# Kilobot_Controller_CPU.net
KiCad netlist of a schematic drawn in Altium Designer
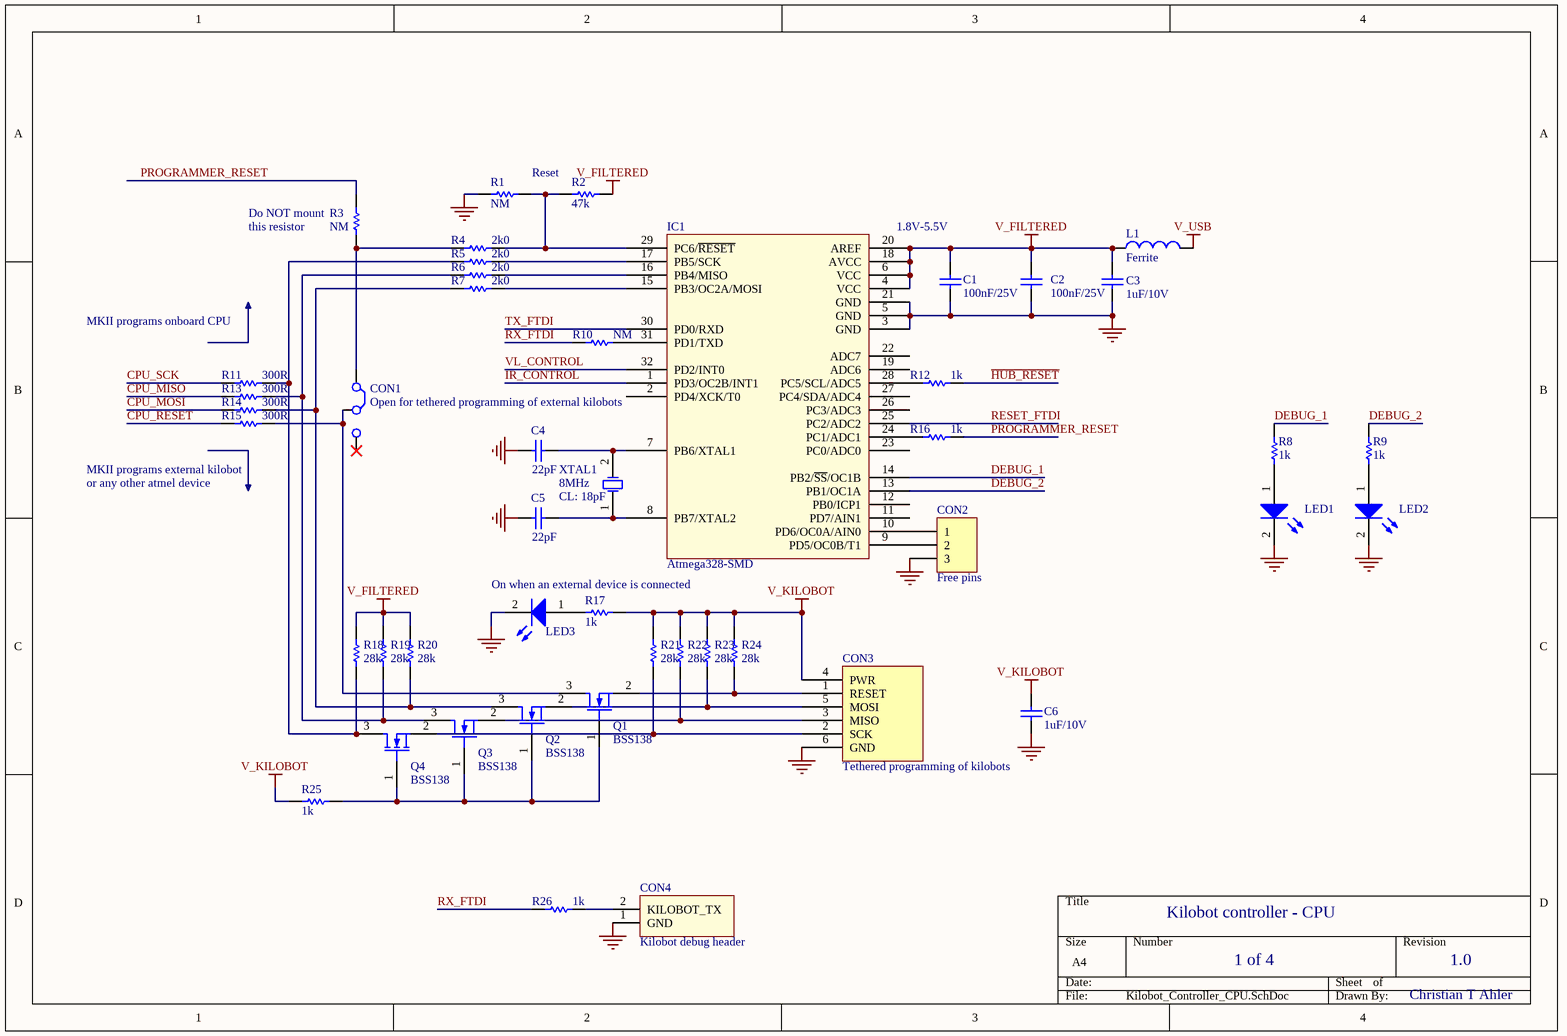
[diagram p0: Kilobot_Controller_CPU.SchDoc]

(export (version "E")
  (design (tool "Eeschema 10.0.6"))
  (components
    (comp (ref "C1")
      (value "100nF/25V")
      (footprint "RESC1608L")
      (description "Ceramic Chip Capacitor - Standard")
      (fields (field (name "Comment") "C0603"))
      (libsource (lib "KEMET Chip Capacitor") (part "C0603"))
    )
    (comp (ref "C2")
      (value "100nF/25V")
      (footprint "RESC1608L")
      (description "Ceramic Chip Capacitor - Standard")
      (fields (field (name "Comment") "C0603"))
      (libsource (lib "KEMET Chip Capacitor") (part "C0603"))
    )
    (comp (ref "C3")
      (value "1uF/10V")
      (footprint "RESC1608L")
      (description "Ceramic Chip Capacitor - Standard")
      (fields (field (name "Comment") "C0603"))
      (libsource (lib "KEMET Chip Capacitor") (part "C0603"))
    )
    (comp (ref "C4")
      (value "22pF")
      (footprint "RESC1608L")
      (description "Ceramic Chip Capacitor - Standard")
      (fields (field (name "Comment") "C0603"))
      (libsource (lib "KEMET Chip Capacitor") (part "C0603"))
    )
    (comp (ref "C5")
      (value "22pF")
      (footprint "RESC1608L")
      (description "Ceramic Chip Capacitor - Standard")
      (fields (field (name "Comment") "C0603"))
      (libsource (lib "KEMET Chip Capacitor") (part "C0603"))
    )
    (comp (ref "C6")
      (value "1uF/10V")
      (footprint "RESC1608L")
      (description "Ceramic Chip Capacitor - Standard")
      (fields (field (name "Comment") "C0603"))
      (libsource (lib "KEMET Chip Capacitor") (part "C0603"))
    )
    (comp (ref "CON1")
      (value "~")
      (footprint "Miscellaneous Connectors:HDR1X3")
      (libsource (lib "Kilobot_Controller") (part "Jumper3"))
    )
    (comp (ref "CON2")
      (value "Free pins")
      (footprint "HDR1X3")
      (description "Header, 3-Pin")
      (libsource (lib "Miscellaneous Connectors") (part "Header 3"))
    )
    (comp (ref "CON3")
      (value "Tethered programming of kilobots")
      (footprint "Programming")
      (libsource (lib "Kilobot_Controller") (part "Programming con new symbol"))
    )
    (comp (ref "CON4")
      (value "Kilobot debug header")
      (footprint "HDR1X2")
      (libsource (lib "Kilobot_Controller") (part "Kilobot_Debug_Header"))
    )
    (comp (ref "IC1")
      (value "Atmega328-SMD")
      (footprint "TQFP32")
      (libsource (lib "Programmer") (part "Atmega328-SMD"))
    )
    (comp (ref "L1")
      (value "Ferrite")
      (footprint "RESC2012N")
      (description "Inductor")
      (libsource (lib "Miscellaneous Devices") (part "Inductor"))
    )
    (comp (ref "LED1") (value "LED") (footprint "LED0603") (libsource (lib "KilobotCommercial") (part "LED")))
    (comp (ref "LED2") (value "LED") (footprint "LED0603") (libsource (lib "KilobotCommercial") (part "LED")))
    (comp (ref "LED3") (value "LED") (footprint "LED0603") (libsource (lib "KilobotCommercial") (part "LED")))
    (comp (ref "Q1")
      (value "BSS138")
      (footprint "sot23-3")
      (fields (field (name "Comment") "NMOS23"))
      (libsource (lib "KilobotCommercial") (part "NMOS23"))
    )
    (comp (ref "Q2")
      (value "BSS138")
      (footprint "sot23-3")
      (fields (field (name "Comment") "NMOS23"))
      (libsource (lib "KilobotCommercial") (part "NMOS23"))
    )
    (comp (ref "Q3")
      (value "BSS138")
      (footprint "sot23-3")
      (fields (field (name "Comment") "NMOS23"))
      (libsource (lib "KilobotCommercial") (part "NMOS23"))
    )
    (comp (ref "Q4")
      (value "BSS138")
      (footprint "sot23-3")
      (fields (field (name "Comment") "NMOS23"))
      (libsource (lib "KilobotCommercial") (part "NMOS23"))
    )
    (comp (ref "R1")
      (value "NM")
      (footprint "RESC1608L")
      (description "Resistor")
      (fields (field (name "Comment") "Res1"))
      (libsource (lib "Miscellaneous Devices") (part "Res1"))
    )
    (comp (ref "R2")
      (value "47k")
      (footprint "RESC1608L")
      (description "Resistor")
      (fields (field (name "Comment") "Res1"))
      (libsource (lib "Miscellaneous Devices") (part "Res1"))
    )
    (comp (ref "R3")
      (value "NM")
      (footprint "RESC1608L")
      (description "Resistor")
      (fields (field (name "Comment") "Res1"))
      (libsource (lib "Miscellaneous Devices") (part "Res1"))
    )
    (comp (ref "R4")
      (value "2k0")
      (footprint "RESC1608L")
      (description "Resistor")
      (fields (field (name "Comment") "Res1"))
      (libsource (lib "Miscellaneous Devices") (part "Res1"))
    )
    (comp (ref "R5")
      (value "2k0")
      (footprint "RESC1608L")
      (description "Resistor")
      (fields (field (name "Comment") "Res1"))
      (libsource (lib "Miscellaneous Devices") (part "Res1"))
    )
    (comp (ref "R6")
      (value "2k0")
      (footprint "RESC1608L")
      (description "Resistor")
      (fields (field (name "Comment") "Res1"))
      (libsource (lib "Miscellaneous Devices") (part "Res1"))
    )
    (comp (ref "R7")
      (value "2k0")
      (footprint "RESC1608L")
      (description "Resistor")
      (fields (field (name "Comment") "Res1"))
      (libsource (lib "Miscellaneous Devices") (part "Res1"))
    )
    (comp (ref "R8")
      (value "1k")
      (footprint "RESC1608L")
      (description "Resistor")
      (fields (field (name "Comment") "Res1"))
      (libsource (lib "Miscellaneous Devices") (part "Res1"))
    )
    (comp (ref "R9")
      (value "1k")
      (footprint "RESC1608L")
      (description "Resistor")
      (fields (field (name "Comment") "Res1"))
      (libsource (lib "Miscellaneous Devices") (part "Res1"))
    )
    (comp (ref "R10")
      (value "NM")
      (footprint "RESC1608L")
      (description "Resistor")
      (fields (field (name "Comment") "Res1"))
      (libsource (lib "Miscellaneous Devices") (part "Res1"))
    )
    (comp (ref "R11")
      (value "300R")
      (footprint "RESC1608L")
      (description "Resistor")
      (fields (field (name "Comment") "Res1"))
      (libsource (lib "Miscellaneous Devices") (part "Res1"))
    )
    (comp (ref "R12")
      (value "1k")
      (footprint "RESC1608L")
      (description "Resistor")
      (fields (field (name "Comment") "Res1"))
      (libsource (lib "Miscellaneous Devices") (part "Res1"))
    )
    (comp (ref "R13")
      (value "300R")
      (footprint "RESC1608L")
      (description "Resistor")
      (fields (field (name "Comment") "Res1"))
      (libsource (lib "Miscellaneous Devices") (part "Res1"))
    )
    (comp (ref "R14")
      (value "300R")
      (footprint "RESC1608L")
      (description "Resistor")
      (fields (field (name "Comment") "Res1"))
      (libsource (lib "Miscellaneous Devices") (part "Res1"))
    )
    (comp (ref "R15")
      (value "300R")
      (footprint "RESC1608L")
      (description "Resistor")
      (fields (field (name "Comment") "Res1"))
      (libsource (lib "Miscellaneous Devices") (part "Res1"))
    )
    (comp (ref "R16")
      (value "1k")
      (footprint "RESC1608L")
      (description "Resistor")
      (fields (field (name "Comment") "Res1"))
      (libsource (lib "Miscellaneous Devices") (part "Res1"))
    )
    (comp (ref "R17")
      (value "1k")
      (footprint "RESC1608L")
      (description "Resistor")
      (fields (field (name "Comment") "Res1"))
      (libsource (lib "Miscellaneous Devices") (part "Res1"))
    )
    (comp (ref "R18")
      (value "28k")
      (footprint "RESC1608L")
      (description "Resistor")
      (fields (field (name "Comment") "Res1"))
      (libsource (lib "Miscellaneous Devices") (part "Res1"))
    )
    (comp (ref "R19")
      (value "28k")
      (footprint "RESC1608L")
      (description "Resistor")
      (fields (field (name "Comment") "Res1"))
      (libsource (lib "Miscellaneous Devices") (part "Res1"))
    )
    (comp (ref "R20")
      (value "28k")
      (footprint "RESC1608L")
      (description "Resistor")
      (fields (field (name "Comment") "Res1"))
      (libsource (lib "Miscellaneous Devices") (part "Res1"))
    )
    (comp (ref "R21")
      (value "28k")
      (footprint "RESC1608L")
      (description "Resistor")
      (fields (field (name "Comment") "Res1"))
      (libsource (lib "Miscellaneous Devices") (part "Res1"))
    )
    (comp (ref "R22")
      (value "28k")
      (footprint "RESC1608L")
      (description "Resistor")
      (fields (field (name "Comment") "Res1"))
      (libsource (lib "Miscellaneous Devices") (part "Res1"))
    )
    (comp (ref "R23")
      (value "28k")
      (footprint "RESC1608L")
      (description "Resistor")
      (fields (field (name "Comment") "Res1"))
      (libsource (lib "Miscellaneous Devices") (part "Res1"))
    )
    (comp (ref "R24")
      (value "28k")
      (footprint "RESC1608L")
      (description "Resistor")
      (fields (field (name "Comment") "Res1"))
      (libsource (lib "Miscellaneous Devices") (part "Res1"))
    )
    (comp (ref "R25")
      (value "1k")
      (footprint "RESC1608L")
      (description "Resistor")
      (fields (field (name "Comment") "Res1"))
      (libsource (lib "Miscellaneous Devices") (part "Res1"))
    )
    (comp (ref "R26")
      (value "1k")
      (footprint "RESC1608L")
      (description "Resistor")
      (fields (field (name "Comment") "Res1"))
      (libsource (lib "Miscellaneous Devices") (part "Res1"))
    )
    (comp (ref "XTAL1")
      (value "8MHz")
      (footprint "crystal-hc49")
      (fields (field (name "CL") "18pF") (field (name "Comment") "Crystal"))
      (libsource (lib "Programmer") (part "Crystal"))
    )
  )
  (nets
    (net (code "1") (name "/CPU_MISO") (class "Default")
      (node (ref "R13") (pin "2") (pinfunction "2_2") (pintype "passive"))
    )
    (net (code "2") (name "/CPU_MOSI") (class "Default")
      (node (ref "R14") (pin "2") (pinfunction "2_2") (pintype "passive"))
    )
    (net (code "3") (name "/CPU_RESET") (class "Default")
      (node (ref "R15") (pin "2") (pinfunction "2_2") (pintype "passive"))
    )
    (net (code "4") (name "/CPU_SCK") (class "Default")
      (node (ref "R11") (pin "2") (pinfunction "2_2") (pintype "passive"))
    )
    (net (code "5") (name "/DEBUG_1") (class "Default")
      (node (ref "IC1") (pin "14") (pinfunction "PB2/~{SS}/OC1B_14") (pintype "passive"))
      (node (ref "R8") (pin "2") (pinfunction "2_2") (pintype "passive"))
    )
    (net (code "6") (name "/DEBUG_2") (class "Default")
      (node (ref "IC1") (pin "13") (pinfunction "PB1/OC1A_13") (pintype "passive"))
      (node (ref "R9") (pin "2") (pinfunction "2_2") (pintype "passive"))
    )
    (net (code "7") (name "/IR_CONTROL") (class "Default")
      (node (ref "IC1") (pin "1") (pinfunction "PD3/OC2B/INT1_1") (pintype "passive"))
    )
    (net (code "8") (name "/PROGRAMMER_RESET") (class "Default")
      (node (ref "R16") (pin "2") (pinfunction "2_2") (pintype "passive"))
      (node (ref "R3") (pin "2") (pinfunction "2_2") (pintype "passive"))
    )
    (net (code "9") (name "/RESET_FTDI") (class "Default")
      (node (ref "IC1") (pin "25") (pinfunction "PC2/ADC2_25") (pintype "passive"))
    )
    (net (code "10") (name "/RX_FTDI") (class "Default")
      (node (ref "R10") (pin "2") (pinfunction "2_2") (pintype "passive"))
      (node (ref "R26") (pin "2") (pinfunction "2_2") (pintype "passive"))
    )
    (net (code "11") (name "/TX_FTDI") (class "Default")
      (node (ref "IC1") (pin "30") (pinfunction "PD0/RXD_30") (pintype "passive"))
    )
    (net (code "12") (name "/VL_CONTROL") (class "Default")
      (node (ref "IC1") (pin "32") (pinfunction "PD2/INT0_32") (pintype "passive"))
    )
    (net (code "13") (name "/~{HUB_RESET}") (class "Default")
      (node (ref "R12") (pin "2") (pinfunction "2_2") (pintype "passive"))
    )
    (net (code "14") (name "GND") (class "Default")
      (node (ref "C1") (pin "2") (pinfunction "2_2") (pintype "passive"))
      (node (ref "C2") (pin "2") (pinfunction "2_2") (pintype "passive"))
      (node (ref "C3") (pin "1") (pinfunction "1_1") (pintype "passive"))
      (node (ref "C4") (pin "1") (pinfunction "1_1") (pintype "passive"))
      (node (ref "C5") (pin "1") (pinfunction "1_1") (pintype "passive"))
      (node (ref "C6") (pin "2") (pinfunction "2_2") (pintype "passive"))
      (node (ref "CON2") (pin "3") (pinfunction "3_3") (pintype "passive"))
      (node (ref "CON3") (pin "6") (pinfunction "GND_6") (pintype "passive"))
      (node (ref "CON4") (pin "1") (pinfunction "GND_1") (pintype "passive"))
      (node (ref "IC1") (pin "21") (pinfunction "GND_21") (pintype "passive"))
      (node (ref "IC1") (pin "3") (pinfunction "GND_3") (pintype "passive"))
      (node (ref "IC1") (pin "5") (pinfunction "GND_5") (pintype "passive"))
      (node (ref "LED1") (pin "2") (pinfunction "K_2") (pintype "passive"))
      (node (ref "LED2") (pin "2") (pinfunction "K_2") (pintype "passive"))
      (node (ref "LED3") (pin "2") (pinfunction "K_2") (pintype "passive"))
      (node (ref "R1") (pin "2") (pinfunction "2_2") (pintype "passive"))
    )
    (net (code "15") (name "Net-(CON1-C1)") (class "Default")
      (node (ref "CON1") (pin "1") (pinfunction "C1_1") (pintype "passive"))
      (node (ref "R3") (pin "1") (pinfunction "1_1") (pintype "passive"))
      (node (ref "R4") (pin "2") (pinfunction "2_2") (pintype "passive"))
    )
    (net (code "16") (name "Net-(CON1-C2)") (class "Default")
      (node (ref "CON1") (pin "2") (pinfunction "C2_2") (pintype "passive"))
      (node (ref "Q1") (pin "3") (pinfunction "D_3") (pintype "passive"))
      (node (ref "R15") (pin "1") (pinfunction "1_1") (pintype "passive"))
    )
    (net (code "17") (name "Net-(CON3-MISO)") (class "Default")
      (node (ref "CON3") (pin "3") (pinfunction "MISO_3") (pintype "passive"))
      (node (ref "Q3") (pin "2") (pinfunction "S_2") (pintype "passive"))
      (node (ref "R22") (pin "1") (pinfunction "1_1") (pintype "passive"))
    )
    (net (code "18") (name "Net-(CON3-MOSI)") (class "Default")
      (node (ref "CON3") (pin "5") (pinfunction "MOSI_5") (pintype "passive"))
      (node (ref "Q2") (pin "2") (pinfunction "S_2") (pintype "passive"))
      (node (ref "R23") (pin "1") (pinfunction "1_1") (pintype "passive"))
    )
    (net (code "19") (name "Net-(CON3-RESET)") (class "Default")
      (node (ref "CON3") (pin "1") (pinfunction "RESET_1") (pintype "passive"))
      (node (ref "Q1") (pin "2") (pinfunction "S_2") (pintype "passive"))
      (node (ref "R24") (pin "1") (pinfunction "1_1") (pintype "passive"))
    )
    (net (code "20") (name "Net-(CON3-SCK)") (class "Default")
      (node (ref "CON3") (pin "2") (pinfunction "SCK_2") (pintype "passive"))
      (node (ref "Q4") (pin "2") (pinfunction "S_2") (pintype "passive"))
      (node (ref "R21") (pin "1") (pinfunction "1_1") (pintype "passive"))
    )
    (net (code "21") (name "Net-(CON4-KILOBOT_TX)") (class "Default")
      (node (ref "CON4") (pin "2") (pinfunction "KILOBOT_TX_2") (pintype "passive"))
      (node (ref "R26") (pin "1") (pinfunction "1_1") (pintype "passive"))
    )
    (net (code "22") (name "Net-(IC1-PB3{slash}OC2A{slash}MOSI)") (class "Default")
      (node (ref "IC1") (pin "15") (pinfunction "PB3/OC2A/MOSI_15") (pintype "passive"))
      (node (ref "R7") (pin "1") (pinfunction "1_1") (pintype "passive"))
    )
    (net (code "23") (name "Net-(IC1-PB4{slash}MISO)") (class "Default")
      (node (ref "IC1") (pin "16") (pinfunction "PB4/MISO_16") (pintype "passive"))
      (node (ref "R6") (pin "1") (pinfunction "1_1") (pintype "passive"))
    )
    (net (code "24") (name "Net-(IC1-PB5{slash}SCK)") (class "Default")
      (node (ref "IC1") (pin "17") (pinfunction "PB5/SCK_17") (pintype "passive"))
      (node (ref "R5") (pin "1") (pinfunction "1_1") (pintype "passive"))
    )
    (net (code "25") (name "Net-(IC1-PB6{slash}XTAL1)") (class "Default")
      (node (ref "C4") (pin "2") (pinfunction "2_2") (pintype "passive"))
      (node (ref "IC1") (pin "7") (pinfunction "PB6/XTAL1_7") (pintype "passive"))
      (node (ref "XTAL1") (pin "2") (pinfunction "OSC2_2") (pintype "passive"))
    )
    (net (code "26") (name "Net-(IC1-PB7{slash}XTAL2)") (class "Default")
      (node (ref "C5") (pin "2") (pinfunction "2_2") (pintype "passive"))
      (node (ref "IC1") (pin "8") (pinfunction "PB7/XTAL2_8") (pintype "passive"))
      (node (ref "XTAL1") (pin "1") (pinfunction "OSC1_1") (pintype "passive"))
    )
    (net (code "27") (name "Net-(IC1-PC1{slash}ADC1)") (class "Default")
      (node (ref "IC1") (pin "24") (pinfunction "PC1/ADC1_24") (pintype "passive"))
      (node (ref "R16") (pin "1") (pinfunction "1_1") (pintype "passive"))
    )
    (net (code "28") (name "Net-(IC1-PC5{slash}SCL{slash}ADC5)") (class "Default")
      (node (ref "IC1") (pin "28") (pinfunction "PC5/SCL/ADC5_28") (pintype "passive"))
      (node (ref "R12") (pin "1") (pinfunction "1_1") (pintype "passive"))
    )
    (net (code "29") (name "Net-(IC1-PC6{slash}~{RESET})") (class "Default")
      (node (ref "IC1") (pin "29") (pinfunction "PC6/~{RESET}_29") (pintype "passive"))
      (node (ref "R1") (pin "1") (pinfunction "1_1") (pintype "passive"))
      (node (ref "R2") (pin "2") (pinfunction "2_2") (pintype "passive"))
      (node (ref "R4") (pin "1") (pinfunction "1_1") (pintype "passive"))
    )
    (net (code "30") (name "Net-(IC1-PD1{slash}TXD)") (class "Default")
      (node (ref "IC1") (pin "31") (pinfunction "PD1/TXD_31") (pintype "passive"))
      (node (ref "R10") (pin "1") (pinfunction "1_1") (pintype "passive"))
    )
    (net (code "31") (name "Net-(IC1-PD5{slash}OC0B{slash}T1)") (class "Default")
      (node (ref "CON2") (pin "2") (pinfunction "2_2") (pintype "passive"))
      (node (ref "IC1") (pin "9") (pinfunction "PD5/OC0B/T1_9") (pintype "passive"))
    )
    (net (code "32") (name "Net-(IC1-PD6{slash}OC0A{slash}AIN0)") (class "Default")
      (node (ref "CON2") (pin "1") (pinfunction "1_1") (pintype "passive"))
      (node (ref "IC1") (pin "10") (pinfunction "PD6/OC0A/AIN0_10") (pintype "passive"))
    )
    (net (code "33") (name "Net-(LED1-A)") (class "Default")
      (node (ref "LED1") (pin "1") (pinfunction "A_1") (pintype "passive"))
      (node (ref "R8") (pin "1") (pinfunction "1_1") (pintype "passive"))
    )
    (net (code "34") (name "Net-(LED2-A)") (class "Default")
      (node (ref "LED2") (pin "1") (pinfunction "A_1") (pintype "passive"))
      (node (ref "R9") (pin "1") (pinfunction "1_1") (pintype "passive"))
    )
    (net (code "35") (name "Net-(LED3-A)") (class "Default")
      (node (ref "LED3") (pin "1") (pinfunction "A_1") (pintype "passive"))
      (node (ref "R17") (pin "2") (pinfunction "2_2") (pintype "passive"))
    )
    (net (code "36") (name "Net-(Q1-G)") (class "Default")
      (node (ref "Q1") (pin "1") (pinfunction "G_1") (pintype "passive"))
      (node (ref "Q2") (pin "1") (pinfunction "G_1") (pintype "passive"))
      (node (ref "Q3") (pin "1") (pinfunction "G_1") (pintype "passive"))
      (node (ref "Q4") (pin "1") (pinfunction "G_1") (pintype "passive"))
      (node (ref "R25") (pin "2") (pinfunction "2_2") (pintype "passive"))
    )
    (net (code "37") (name "Net-(Q2-D)") (class "Default")
      (node (ref "Q2") (pin "3") (pinfunction "D_3") (pintype "passive"))
      (node (ref "R14") (pin "1") (pinfunction "1_1") (pintype "passive"))
      (node (ref "R20") (pin "1") (pinfunction "1_1") (pintype "passive"))
      (node (ref "R7") (pin "2") (pinfunction "2_2") (pintype "passive"))
    )
    (net (code "38") (name "Net-(Q3-D)") (class "Default")
      (node (ref "Q3") (pin "3") (pinfunction "D_3") (pintype "passive"))
      (node (ref "R13") (pin "1") (pinfunction "1_1") (pintype "passive"))
      (node (ref "R19") (pin "1") (pinfunction "1_1") (pintype "passive"))
      (node (ref "R6") (pin "2") (pinfunction "2_2") (pintype "passive"))
    )
    (net (code "39") (name "Net-(Q4-D)") (class "Default")
      (node (ref "Q4") (pin "3") (pinfunction "D_3") (pintype "passive"))
      (node (ref "R11") (pin "1") (pinfunction "1_1") (pintype "passive"))
      (node (ref "R18") (pin "1") (pinfunction "1_1") (pintype "passive"))
      (node (ref "R5") (pin "2") (pinfunction "2_2") (pintype "passive"))
    )
    (net (code "40") (name "V_FILTERED") (class "Default")
      (node (ref "C1") (pin "1") (pinfunction "1_1") (pintype "passive"))
      (node (ref "C2") (pin "1") (pinfunction "1_1") (pintype "passive"))
      (node (ref "C3") (pin "2") (pinfunction "2_2") (pintype "passive"))
      (node (ref "IC1") (pin "18") (pinfunction "AVCC_18") (pintype "passive"))
      (node (ref "IC1") (pin "20") (pinfunction "AREF_20") (pintype "passive"))
      (node (ref "IC1") (pin "4") (pinfunction "VCC_4") (pintype "passive"))
      (node (ref "IC1") (pin "6") (pinfunction "VCC_6") (pintype "passive"))
      (node (ref "L1") (pin "1") (pinfunction "1_1") (pintype "passive"))
      (node (ref "R18") (pin "2") (pinfunction "2_2") (pintype "passive"))
      (node (ref "R19") (pin "2") (pinfunction "2_2") (pintype "passive"))
      (node (ref "R2") (pin "1") (pinfunction "1_1") (pintype "passive"))
      (node (ref "R20") (pin "2") (pinfunction "2_2") (pintype "passive"))
    )
    (net (code "41") (name "V_KILOBOT") (class "Default")
      (node (ref "C6") (pin "1") (pinfunction "1_1") (pintype "passive"))
      (node (ref "CON3") (pin "4") (pinfunction "PWR_4") (pintype "passive"))
      (node (ref "R17") (pin "1") (pinfunction "1_1") (pintype "passive"))
      (node (ref "R21") (pin "2") (pinfunction "2_2") (pintype "passive"))
      (node (ref "R22") (pin "2") (pinfunction "2_2") (pintype "passive"))
      (node (ref "R23") (pin "2") (pinfunction "2_2") (pintype "passive"))
      (node (ref "R24") (pin "2") (pinfunction "2_2") (pintype "passive"))
      (node (ref "R25") (pin "1") (pinfunction "1_1") (pintype "passive"))
    )
    (net (code "42") (name "V_USB") (class "Default")
      (node (ref "L1") (pin "2") (pinfunction "2_2") (pintype "passive"))
    )
    (net (code "43") (name "unconnected-(CON1-C3-Pad3)") (class "Default")
      (node (ref "CON1") (pin "3") (pinfunction "C3_3") (pintype "passive+no_connect"))
    )
    (net (code "44") (name "unconnected-(IC1-ADC6-Pad19)") (class "Default")
      (node (ref "IC1") (pin "19") (pinfunction "ADC6_19") (pintype "passive"))
    )
    (net (code "45") (name "unconnected-(IC1-ADC7-Pad22)") (class "Default")
      (node (ref "IC1") (pin "22") (pinfunction "ADC7_22") (pintype "passive"))
    )
    (net (code "46") (name "unconnected-(IC1-PB0{slash}ICP1-Pad12)") (class "Default")
      (node (ref "IC1") (pin "12") (pinfunction "PB0/ICP1_12") (pintype "passive"))
    )
    (net (code "47") (name "unconnected-(IC1-PC0{slash}ADC0-Pad23)") (class "Default")
      (node (ref "IC1") (pin "23") (pinfunction "PC0/ADC0_23") (pintype "passive"))
    )
    (net (code "48") (name "unconnected-(IC1-PC3{slash}ADC3-Pad26)") (class "Default")
      (node (ref "IC1") (pin "26") (pinfunction "PC3/ADC3_26") (pintype "passive"))
    )
    (net (code "49") (name "unconnected-(IC1-PC4{slash}SDA{slash}ADC4-Pad27)") (class "Default")
      (node (ref "IC1") (pin "27") (pinfunction "PC4/SDA/ADC4_27") (pintype "passive"))
    )
    (net (code "50") (name "unconnected-(IC1-PD4{slash}XCK{slash}T0-Pad2)") (class "Default")
      (node (ref "IC1") (pin "2") (pinfunction "PD4/XCK/T0_2") (pintype "passive"))
    )
    (net (code "51") (name "unconnected-(IC1-PD7{slash}AIN1-Pad11)") (class "Default")
      (node (ref "IC1") (pin "11") (pinfunction "PD7/AIN1_11") (pintype "passive"))
    )
  )
)
